# TempControl.net
KiCad netlist of a schematic drawn in EAGLE
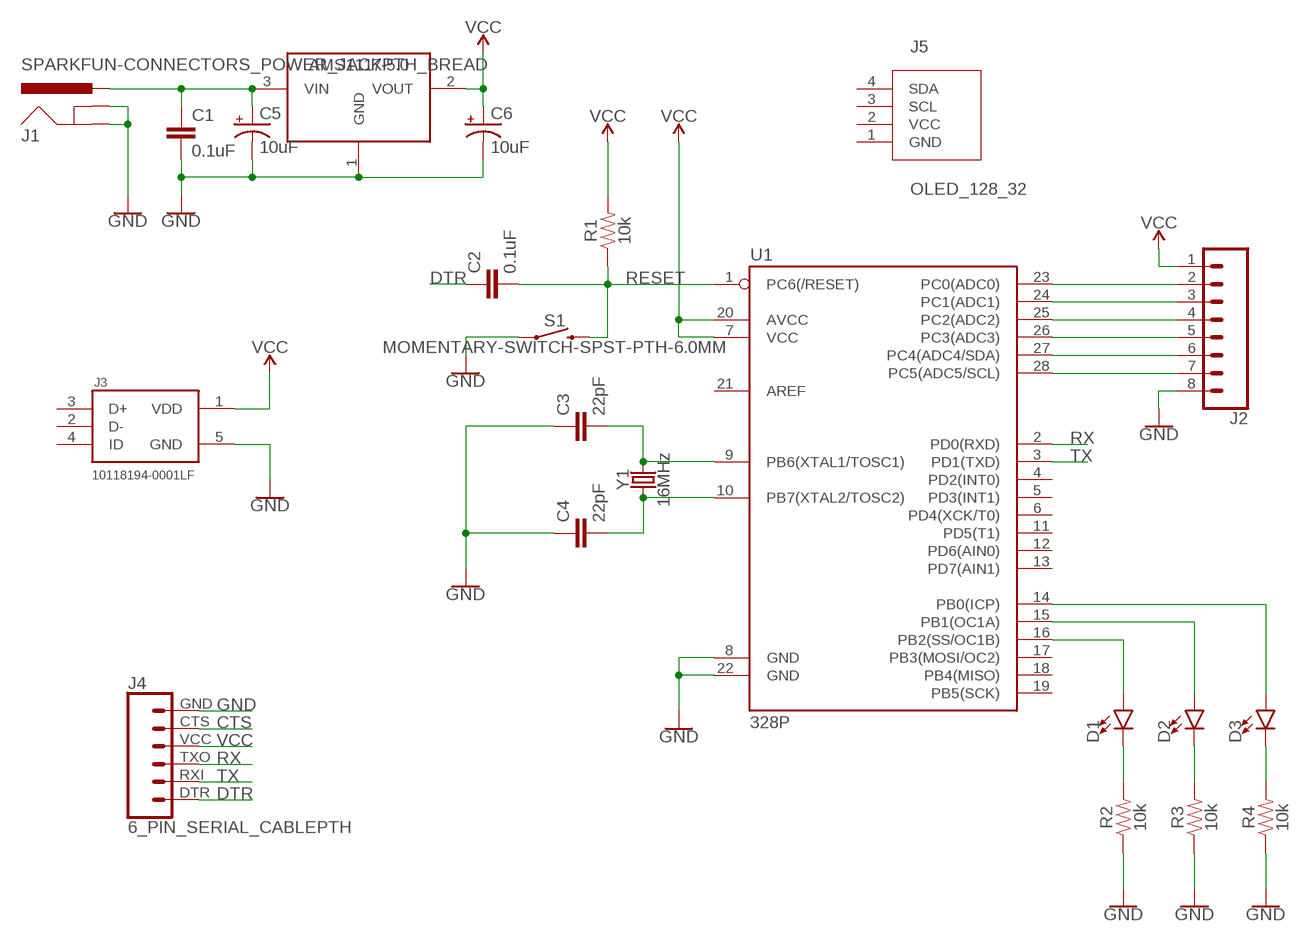
[diagram p0: schematic, sheet 1]

(export (version "E")
  (design (tool "Eeschema 10.0.6"))
  (components
    (comp (ref "C1")
      (value "0.1uF")
      (footprint "eagle-import:CAP-PTH-SMALL-KIT")
      (libsource (lib "eagle-import") (part "0.1UF-KIT-EZ-50V-20%"))
    )
    (comp (ref "C2")
      (value "0.1uF")
      (footprint "eagle-import:CAP-PTH-SMALL-KIT")
      (libsource (lib "eagle-import") (part "0.1UF-KIT-EZ-50V-20%"))
    )
    (comp (ref "C3")
      (value "22pF")
      (footprint "eagle-import:CAP-PTH-2.54")
      (libsource (lib "eagle-import") (part "22PF-PTH-2.54MM-200V-5%"))
    )
    (comp (ref "C4")
      (value "22pF")
      (footprint "eagle-import:CAP-PTH-2.54")
      (libsource (lib "eagle-import") (part "22PF-PTH-2.54MM-200V-5%"))
    )
    (comp (ref "C5")
      (value "10uF")
      (footprint "eagle-import:CPOL-RADIAL-2.5MM-5MM")
      (libsource (lib "eagle-import") (part "10UF-POLAR-RADIAL-2.5MM-25V-20%"))
    )
    (comp (ref "C6")
      (value "10uF")
      (footprint "eagle-import:CPOL-RADIAL-2.5MM-5MM")
      (libsource (lib "eagle-import") (part "10UF-POLAR-RADIAL-2.5MM-25V-20%"))
    )
    (comp (ref "D1")
      (value "LED5MM")
      (footprint "eagle-import:LED_5MM")
      (libsource (lib "eagle-import") (part "LED5MM"))
    )
    (comp (ref "D2")
      (value "LED5MM")
      (footprint "eagle-import:LED_5MM")
      (libsource (lib "eagle-import") (part "LED5MM"))
    )
    (comp (ref "D3")
      (value "LED5MM")
      (footprint "eagle-import:LED_5MM")
      (libsource (lib "eagle-import") (part "LED5MM"))
    )
    (comp (ref "J1")
      (value "SPARKFUN-CONNECTORS_POWER_JACKPTH_BREAD")
      (footprint "eagle-import:SPARKFUN-CONNECTORS_POWER_JACK_PTH_BREAD")
      (libsource (lib "eagle-import") (part "SPARKFUN-CONNECTORS_POWER_JACKPTH_BREAD"))
    )
    (comp (ref "J2")
      (value "CONN_08\"")
      (footprint "eagle-import:1X08")
      (libsource (lib "eagle-import") (part "CONN_08{dblquote}"))
    )
    (comp (ref "J3")
      (value "10118194-0001LF")
      (footprint "eagle-import:FRAMATOME_10118194-0001LF")
      (fields (field (name "MF") "Amphenol"))
      (libsource (lib "eagle-import") (part "10118194-0001LF"))
    )
    (comp (ref "J4")
      (value "6_PIN_SERIAL_CABLEPTH")
      (footprint "eagle-import:FTDI_BASIC")
      (libsource (lib "eagle-import") (part "6_PIN_SERIAL_CABLEPTH"))
    )
    (comp (ref "J5")
      (value "OLED_128_32")
      (footprint "eagle-import:OLED_128_32")
      (libsource (lib "eagle-import") (part "OLED_128_32"))
    )
    (comp (ref "R1")
      (value "10k")
      (footprint "eagle-import:AXIAL-0.3")
      (libsource (lib "eagle-import") (part "10KOHM-HORIZ-1/4W-1%"))
    )
    (comp (ref "R2")
      (value "10k")
      (footprint "eagle-import:AXIAL-0.3")
      (libsource (lib "eagle-import") (part "10KOHM-HORIZ-1/4W-1%"))
    )
    (comp (ref "R3")
      (value "10k")
      (footprint "eagle-import:AXIAL-0.3")
      (libsource (lib "eagle-import") (part "10KOHM-HORIZ-1/4W-1%"))
    )
    (comp (ref "R4")
      (value "10k")
      (footprint "eagle-import:AXIAL-0.3")
      (libsource (lib "eagle-import") (part "10KOHM-HORIZ-1/4W-1%"))
    )
    (comp (ref "S1")
      (value "MOMENTARY-SWITCH-SPST-PTH-6.0MM")
      (footprint "eagle-import:TACTILE_SWITCH_PTH_6.0MM")
      (libsource (lib "eagle-import") (part "MOMENTARY-SWITCH-SPST-PTH-6.0MM"))
    )
    (comp (ref "U$1")
      (value "AMS1117-5.0")
      (footprint "eagle-import:SOT223")
      (fields (field (name "MF") "ams"))
      (libsource (lib "eagle-import") (part "AMS1117-5.0"))
    )
    (comp (ref "U1")
      (value "328P")
      (footprint "eagle-import:DIP28")
      (libsource (lib "eagle-import") (part "ATMEGA328P_PDIP"))
    )
    (comp (ref "Y1")
      (value "16MHz")
      (footprint "eagle-import:HC49US")
      (libsource (lib "eagle-import") (part "CRYSTAL-16MHZPTH-HC49US"))
    )
  )
  (nets
    (net (code "1") (name "/CTS") (class "Default")
      (node (ref "J4") (pin "CTS") (pinfunction "5_CTS") (pintype "passive"))
    )
    (net (code "2") (name "/DTR") (class "Default")
      (node (ref "C2") (pin "1") (pinfunction "1_1") (pintype "passive"))
      (node (ref "J4") (pin "DTR") (pinfunction "1_DTR") (pintype "passive"))
    )
    (net (code "3") (name "/RESET") (class "Default")
      (node (ref "C2") (pin "2") (pinfunction "2_2") (pintype "passive"))
      (node (ref "R1") (pin "P$1") (pinfunction "1_P$1") (pintype "passive"))
      (node (ref "S1") (pin "3") (pinfunction "2_3") (pintype "passive"))
      (node (ref "U1") (pin "1") (pinfunction "PC6(/RESET)_1") (pintype "bidirectional"))
    )
    (net (code "4") (name "/RX") (class "Default")
      (node (ref "J4") (pin "TXO") (pinfunction "3_TXO") (pintype "passive"))
      (node (ref "U1") (pin "2") (pinfunction "PD0(RXD)_2") (pintype "bidirectional"))
    )
    (net (code "5") (name "/TX") (class "Default")
      (node (ref "J4") (pin "RXI") (pinfunction "2_RXI") (pintype "passive"))
      (node (ref "U1") (pin "3") (pinfunction "PD1(TXD)_3") (pintype "bidirectional"))
    )
    (net (code "6") (name "GND") (class "Default")
      (node (ref "C1") (pin "2") (pinfunction "2_2") (pintype "passive"))
      (node (ref "C3") (pin "1") (pinfunction "1_1") (pintype "passive"))
      (node (ref "C4") (pin "1") (pinfunction "1_1") (pintype "passive"))
      (node (ref "C5") (pin "2") (pinfunction "-_2") (pintype "passive"))
      (node (ref "C6") (pin "2") (pinfunction "-_2") (pintype "passive"))
      (node (ref "J1") (pin "GND") (pinfunction "GND_GND") (pintype "bidirectional"))
      (node (ref "J1") (pin "GNDBREAK") (pinfunction "GNDBREAK_GNDBREAK") (pintype "bidirectional"))
      (node (ref "J2") (pin "8") (pinfunction "8_8") (pintype "passive"))
      (node (ref "J3") (pin "5") (pinfunction "GND_5") (pintype "power_in"))
      (node (ref "J4") (pin "GND") (pinfunction "6_GND") (pintype "passive"))
      (node (ref "R2") (pin "P$1") (pinfunction "1_P$1") (pintype "passive"))
      (node (ref "R3") (pin "P$1") (pinfunction "1_P$1") (pintype "passive"))
      (node (ref "R4") (pin "P$1") (pinfunction "1_P$1") (pintype "passive"))
      (node (ref "S1") (pin "1") (pinfunction "1_1") (pintype "passive"))
      (node (ref "U$1") (pin "1") (pinfunction "GND_1") (pintype "bidirectional"))
      (node (ref "U1") (pin "22") (pinfunction "GND_22") (pintype "bidirectional"))
      (node (ref "U1") (pin "8") (pinfunction "GND_8") (pintype "bidirectional"))
    )
    (net (code "7") (name "Net-(C5-+)") (class "Default")
      (node (ref "C1") (pin "1") (pinfunction "1_1") (pintype "passive"))
      (node (ref "C5") (pin "1") (pinfunction "+_1") (pintype "passive"))
      (node (ref "J1") (pin "PWR") (pinfunction "PWR_PWR") (pintype "bidirectional"))
      (node (ref "U$1") (pin "3") (pinfunction "VIN_3") (pintype "bidirectional"))
    )
    (net (code "8") (name "Net-(D1-C)") (class "Default")
      (node (ref "D1") (pin "K") (pinfunction "C_K") (pintype "passive"))
      (node (ref "R2") (pin "P$2") (pinfunction "2_P$2") (pintype "passive"))
    )
    (net (code "9") (name "Net-(D2-C)") (class "Default")
      (node (ref "D2") (pin "K") (pinfunction "C_K") (pintype "passive"))
      (node (ref "R3") (pin "P$2") (pinfunction "2_P$2") (pintype "passive"))
    )
    (net (code "10") (name "Net-(D3-C)") (class "Default")
      (node (ref "D3") (pin "K") (pinfunction "C_K") (pintype "passive"))
      (node (ref "R4") (pin "P$2") (pinfunction "2_P$2") (pintype "passive"))
    )
    (net (code "11") (name "Net-(U1-PB0(ICP))") (class "Default")
      (node (ref "D3") (pin "A") (pinfunction "A_A") (pintype "passive"))
      (node (ref "U1") (pin "14") (pinfunction "PB0(ICP)_14") (pintype "bidirectional"))
    )
    (net (code "12") (name "Net-(U1-PB1(OC1A))") (class "Default")
      (node (ref "D2") (pin "A") (pinfunction "A_A") (pintype "passive"))
      (node (ref "U1") (pin "15") (pinfunction "PB1(OC1A)_15") (pintype "bidirectional"))
    )
    (net (code "13") (name "Net-(U1-PB2(SS{slash}OC1B))") (class "Default")
      (node (ref "D1") (pin "A") (pinfunction "A_A") (pintype "passive"))
      (node (ref "U1") (pin "16") (pinfunction "PB2(SS/OC1B)_16") (pintype "bidirectional"))
    )
    (net (code "14") (name "Net-(U1-PB6(XTAL1{slash}TOSC1))") (class "Default")
      (node (ref "C3") (pin "2") (pinfunction "2_2") (pintype "passive"))
      (node (ref "U1") (pin "9") (pinfunction "PB6(XTAL1/TOSC1)_9") (pintype "bidirectional"))
      (node (ref "Y1") (pin "2") (pinfunction "2_2") (pintype "passive"))
    )
    (net (code "15") (name "Net-(U1-PB7(XTAL2{slash}TOSC2))") (class "Default")
      (node (ref "C4") (pin "2") (pinfunction "2_2") (pintype "passive"))
      (node (ref "U1") (pin "10") (pinfunction "PB7(XTAL2/TOSC2)_10") (pintype "bidirectional"))
      (node (ref "Y1") (pin "1") (pinfunction "1_1") (pintype "passive"))
    )
    (net (code "16") (name "Net-(U1-PC0(ADC0))") (class "Default")
      (node (ref "J2") (pin "2") (pinfunction "2_2") (pintype "passive"))
      (node (ref "U1") (pin "23") (pinfunction "PC0(ADC0)_23") (pintype "bidirectional"))
    )
    (net (code "17") (name "Net-(U1-PC1(ADC1))") (class "Default")
      (node (ref "J2") (pin "3") (pinfunction "3_3") (pintype "passive"))
      (node (ref "U1") (pin "24") (pinfunction "PC1(ADC1)_24") (pintype "bidirectional"))
    )
    (net (code "18") (name "Net-(U1-PC2(ADC2))") (class "Default")
      (node (ref "J2") (pin "4") (pinfunction "4_4") (pintype "passive"))
      (node (ref "U1") (pin "25") (pinfunction "PC2(ADC2)_25") (pintype "bidirectional"))
    )
    (net (code "19") (name "Net-(U1-PC3(ADC3))") (class "Default")
      (node (ref "J2") (pin "5") (pinfunction "5_5") (pintype "passive"))
      (node (ref "U1") (pin "26") (pinfunction "PC3(ADC3)_26") (pintype "bidirectional"))
    )
    (net (code "20") (name "Net-(U1-PC4(ADC4{slash}SDA))") (class "Default")
      (node (ref "J2") (pin "6") (pinfunction "6_6") (pintype "passive"))
      (node (ref "U1") (pin "27") (pinfunction "PC4(ADC4/SDA)_27") (pintype "bidirectional"))
    )
    (net (code "21") (name "Net-(U1-PC5(ADC5{slash}SCL))") (class "Default")
      (node (ref "J2") (pin "7") (pinfunction "7_7") (pintype "passive"))
      (node (ref "U1") (pin "28") (pinfunction "PC5(ADC5/SCL)_28") (pintype "bidirectional"))
    )
    (net (code "22") (name "VCC") (class "Default")
      (node (ref "C6") (pin "1") (pinfunction "+_1") (pintype "passive"))
      (node (ref "J2") (pin "1") (pinfunction "1_1") (pintype "passive"))
      (node (ref "J3") (pin "1") (pinfunction "VDD_1") (pintype "power_in"))
      (node (ref "J4") (pin "VCC") (pinfunction "4_VCC") (pintype "passive"))
      (node (ref "R1") (pin "P$2") (pinfunction "2_P$2") (pintype "passive"))
      (node (ref "U$1") (pin "2") (pinfunction "VOUT_2") (pintype "bidirectional"))
      (node (ref "U1") (pin "20") (pinfunction "AVCC_20") (pintype "bidirectional"))
      (node (ref "U1") (pin "7") (pinfunction "VCC_7") (pintype "bidirectional"))
    )
    (net (code "23") (name "unconnected-(J3-D+-Pad3)") (class "Default")
      (node (ref "J3") (pin "3") (pinfunction "D+_3") (pintype "bidirectional"))
    )
    (net (code "24") (name "unconnected-(J3-D--Pad2)") (class "Default")
      (node (ref "J3") (pin "2") (pinfunction "D-_2") (pintype "bidirectional"))
    )
    (net (code "25") (name "unconnected-(J3-ID-Pad4)") (class "Default")
      (node (ref "J3") (pin "4") (pinfunction "ID_4") (pintype "passive"))
    )
    (net (code "26") (name "unconnected-(J5-GND-Pad1)") (class "Default")
      (node (ref "J5") (pin "1") (pinfunction "GND_1") (pintype "bidirectional"))
    )
    (net (code "27") (name "unconnected-(J5-SCL-Pad3)") (class "Default")
      (node (ref "J5") (pin "3") (pinfunction "SCL_3") (pintype "bidirectional"))
    )
    (net (code "28") (name "unconnected-(J5-SDA-Pad4)") (class "Default")
      (node (ref "J5") (pin "4") (pinfunction "SDA_4") (pintype "bidirectional"))
    )
    (net (code "29") (name "unconnected-(J5-VCC-Pad2)") (class "Default")
      (node (ref "J5") (pin "2") (pinfunction "VCC_2") (pintype "bidirectional"))
    )
    (net (code "30") (name "unconnected-(U1-AREF-Pad21)") (class "Default")
      (node (ref "U1") (pin "21") (pinfunction "AREF_21") (pintype "bidirectional"))
    )
    (net (code "31") (name "unconnected-(U1-PB3(MOSI{slash}OC2)-Pad17)") (class "Default")
      (node (ref "U1") (pin "17") (pinfunction "PB3(MOSI/OC2)_17") (pintype "bidirectional"))
    )
    (net (code "32") (name "unconnected-(U1-PB4(MISO)-Pad18)") (class "Default")
      (node (ref "U1") (pin "18") (pinfunction "PB4(MISO)_18") (pintype "bidirectional"))
    )
    (net (code "33") (name "unconnected-(U1-PB5(SCK)-Pad19)") (class "Default")
      (node (ref "U1") (pin "19") (pinfunction "PB5(SCK)_19") (pintype "bidirectional"))
    )
    (net (code "34") (name "unconnected-(U1-PD2(INT0)-Pad4)") (class "Default")
      (node (ref "U1") (pin "4") (pinfunction "PD2(INT0)_4") (pintype "bidirectional"))
    )
    (net (code "35") (name "unconnected-(U1-PD3(INT1)-Pad5)") (class "Default")
      (node (ref "U1") (pin "5") (pinfunction "PD3(INT1)_5") (pintype "bidirectional"))
    )
    (net (code "36") (name "unconnected-(U1-PD4(XCK{slash}T0)-Pad6)") (class "Default")
      (node (ref "U1") (pin "6") (pinfunction "PD4(XCK/T0)_6") (pintype "bidirectional"))
    )
    (net (code "37") (name "unconnected-(U1-PD5(T1)-Pad11)") (class "Default")
      (node (ref "U1") (pin "11") (pinfunction "PD5(T1)_11") (pintype "bidirectional"))
    )
    (net (code "38") (name "unconnected-(U1-PD6(AIN0)-Pad12)") (class "Default")
      (node (ref "U1") (pin "12") (pinfunction "PD6(AIN0)_12") (pintype "bidirectional"))
    )
    (net (code "39") (name "unconnected-(U1-PD7(AIN1)-Pad13)") (class "Default")
      (node (ref "U1") (pin "13") (pinfunction "PD7(AIN1)_13") (pintype "bidirectional"))
    )
  )
)
